# SCH_TDA-Audio-Amplifier_2024-02-14.net
KiCad netlist of a schematic drawn in EasyEDA
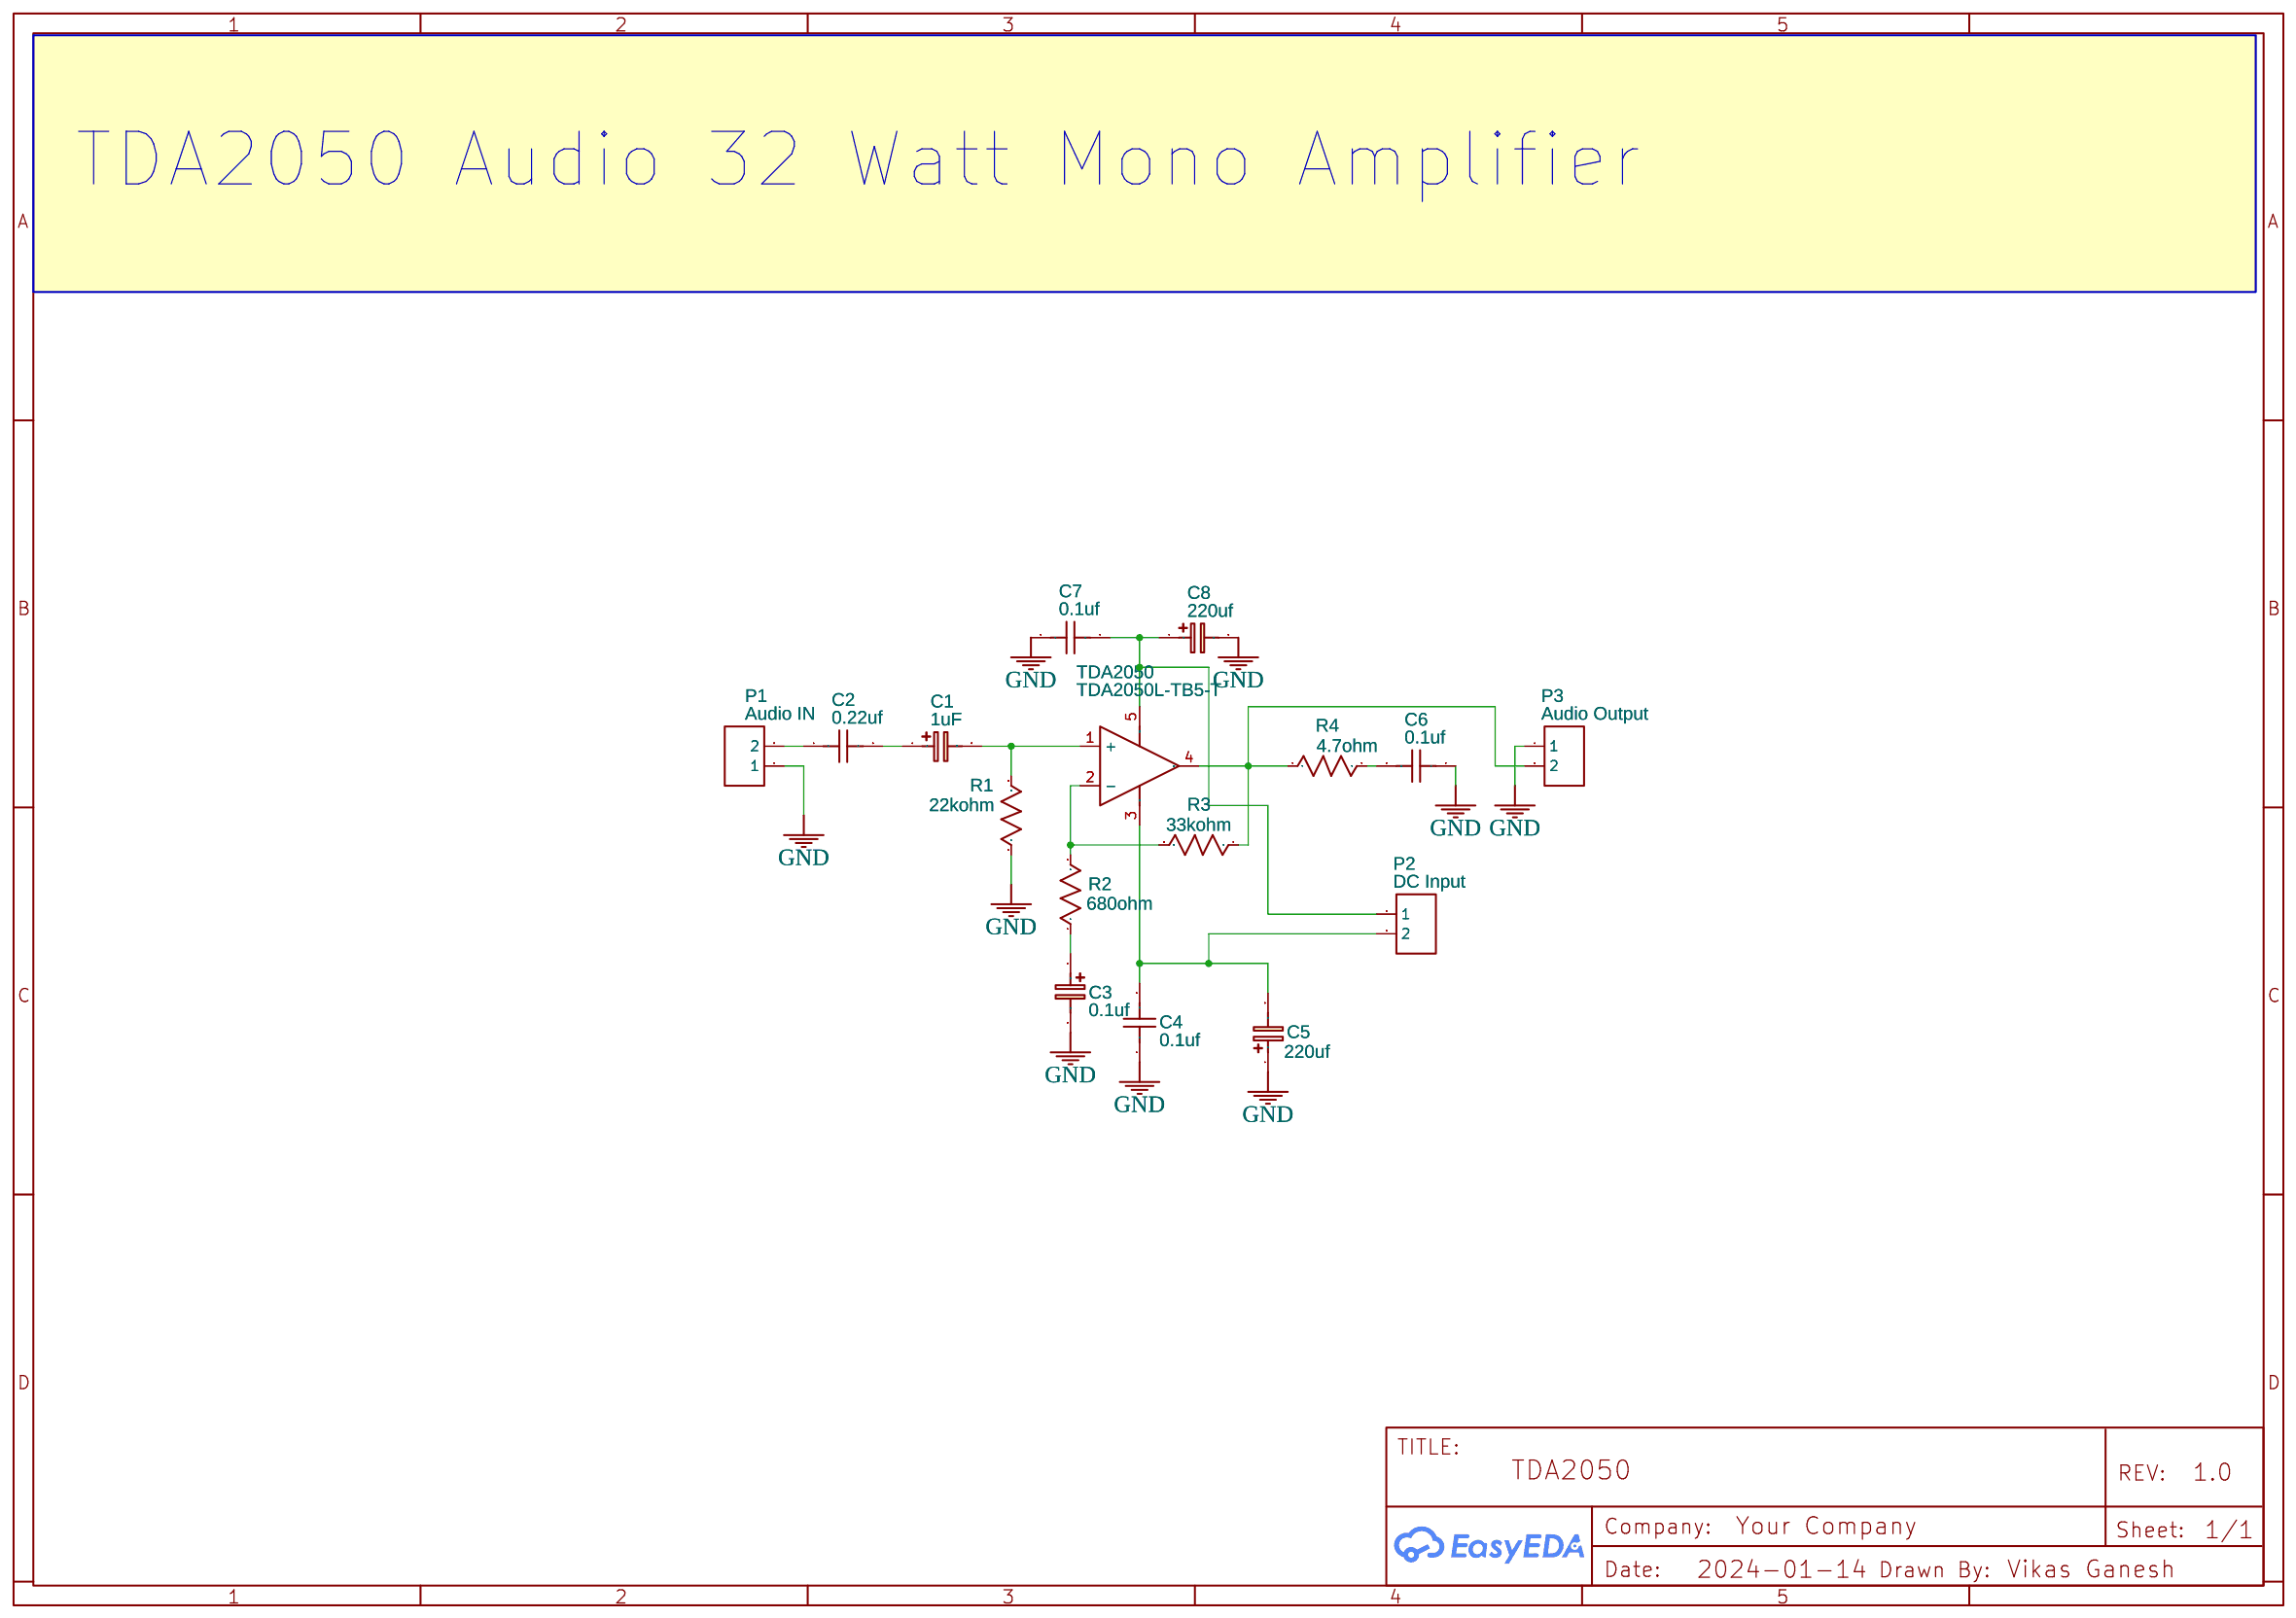
[diagram p0: schematic sheet]

(export (version "E")
  (design (tool "Eeschema 10.0.6"))
  (components
    (comp (ref "C1") (value "1uF") (libsource (lib "") (part "CE_TH_D4.0×F1.5_EU_1")))
    (comp (ref "C2") (value "0.22uf") (libsource (lib "") (part "C_RAD-0.1_US_2")))
    (comp (ref "C3") (value "0.1uf") (libsource (lib "") (part "CE_TH_D4.0×F1.5_EU")))
    (comp (ref "C4") (value "0.1uf") (libsource (lib "") (part "C_RAD-0.1_US_1")))
    (comp (ref "C5") (value "220uf") (libsource (lib "") (part "CE_TH_D4.0×F1.5_EU_3")))
    (comp (ref "C6") (value "0.1uf") (libsource (lib "") (part "C_RAD-0.1_US")))
    (comp (ref "C7") (value "0.1uf") (libsource (lib "") (part "C_RAD-0.1_US")))
    (comp (ref "C8") (value "220uf") (libsource (lib "") (part "CE_TH_D4.0×F1.5_EU_2")))
    (comp (ref "P1") (value "Audio IN") (libsource (lib "") (part "CONN-TH_2P-P5.00_1")))
    (comp (ref "P2") (value "DC Input") (libsource (lib "") (part "CONN-TH_2P-P5.00")))
    (comp (ref "P3") (value "Audio Output") (libsource (lib "") (part "CONN-TH_2P-P5.00")))
    (comp (ref "R1") (value "22kohm") (libsource (lib "") (part "R_AXIAL-0.4_US_2")))
    (comp (ref "R2") (value "680ohm") (libsource (lib "") (part "R_AXIAL-0.4_US_2")))
    (comp (ref "R3") (value "33kohm") (libsource (lib "") (part "R_AXIAL-0.4_US_1")))
    (comp (ref "R4") (value "4.7ohm") (libsource (lib "") (part "R_AXIAL-0.4_US")))
    (comp (ref "TDA2050")
      (value "TDA2050L-TB5-T")
      (fields (field (name "Manufacturer") "UTC(友顺)"))
      (libsource (lib "") (part "TDA2050L-TB5-T"))
    )
  )
  (nets
    (net (code "1") (name "GND") (class "Default")
      (node (ref "C3") (pin "2") (pinfunction "2_2") (pintype "unspecified"))
      (node (ref "C4") (pin "1") (pinfunction "1_1") (pintype "unspecified"))
      (node (ref "C5") (pin "1") (pinfunction "1_1") (pintype "unspecified"))
      (node (ref "C6") (pin "1") (pinfunction "1_1") (pintype "unspecified"))
      (node (ref "C7") (pin "2") (pinfunction "2_2") (pintype "unspecified"))
      (node (ref "C8") (pin "2") (pinfunction "2_2") (pintype "unspecified"))
      (node (ref "P1") (pin "1") (pinfunction "1_1") (pintype "unspecified"))
      (node (ref "P3") (pin "1") (pinfunction "1_1") (pintype "unspecified"))
      (node (ref "R1") (pin "1") (pinfunction "1_1") (pintype "unspecified"))
    )
    (net (code "2") (name "Net-(C1-Pad1)") (class "Default")
      (node (ref "C1") (pin "1") (pinfunction "1_1") (pintype "unspecified"))
      (node (ref "C2") (pin "2") (pinfunction "2_2") (pintype "unspecified"))
    )
    (net (code "3") (name "Net-(C2-Pad1)") (class "Default")
      (node (ref "C2") (pin "1") (pinfunction "1_1") (pintype "unspecified"))
      (node (ref "P1") (pin "2") (pinfunction "2_2") (pintype "unspecified"))
    )
    (net (code "4") (name "Net-(C3-Pad1)") (class "Default")
      (node (ref "C3") (pin "1") (pinfunction "1_1") (pintype "unspecified"))
      (node (ref "R2") (pin "1") (pinfunction "1_1") (pintype "unspecified"))
    )
    (net (code "5") (name "Net-(C6-Pad2)") (class "Default")
      (node (ref "C6") (pin "2") (pinfunction "2_2") (pintype "unspecified"))
      (node (ref "R4") (pin "2") (pinfunction "2_2") (pintype "unspecified"))
    )
    (net (code "6") (name "Net-(TDA2050-+)") (class "Default")
      (node (ref "C1") (pin "2") (pinfunction "2_2") (pintype "unspecified"))
      (node (ref "R1") (pin "2") (pinfunction "2_2") (pintype "unspecified"))
      (node (ref "TDA2050") (pin "1") (pinfunction "+_1") (pintype "unspecified"))
    )
    (net (code "7") (name "Net-(TDA2050--)") (class "Default")
      (node (ref "R2") (pin "2") (pinfunction "2_2") (pintype "unspecified"))
      (node (ref "R3") (pin "2") (pinfunction "2_2") (pintype "unspecified"))
      (node (ref "TDA2050") (pin "2") (pinfunction "-_2") (pintype "unspecified"))
    )
    (net (code "8") (name "Net-(TDA2050-GND)") (class "Default")
      (node (ref "C4") (pin "2") (pinfunction "2_2") (pintype "unspecified"))
      (node (ref "C5") (pin "2") (pinfunction "2_2") (pintype "unspecified"))
      (node (ref "P2") (pin "2") (pinfunction "2_2") (pintype "unspecified"))
      (node (ref "TDA2050") (pin "3") (pinfunction "GND_3") (pintype "unspecified"))
    )
    (net (code "9") (name "Net-(TDA2050-OUT)") (class "Default")
      (node (ref "P3") (pin "2") (pinfunction "2_2") (pintype "unspecified"))
      (node (ref "R3") (pin "1") (pinfunction "1_1") (pintype "unspecified"))
      (node (ref "R4") (pin "1") (pinfunction "1_1") (pintype "unspecified"))
      (node (ref "TDA2050") (pin "4") (pinfunction "OUT_4") (pintype "unspecified"))
    )
    (net (code "10") (name "Net-(TDA2050-VCC+)") (class "Default")
      (node (ref "C7") (pin "1") (pinfunction "1_1") (pintype "unspecified"))
      (node (ref "C8") (pin "1") (pinfunction "1_1") (pintype "unspecified"))
      (node (ref "P2") (pin "1") (pinfunction "1_1") (pintype "unspecified"))
      (node (ref "TDA2050") (pin "5") (pinfunction "VCC+_5") (pintype "unspecified"))
    )
  )
)
